# power_rev_1.net
KiCad netlist of a schematic drawn in EAGLE
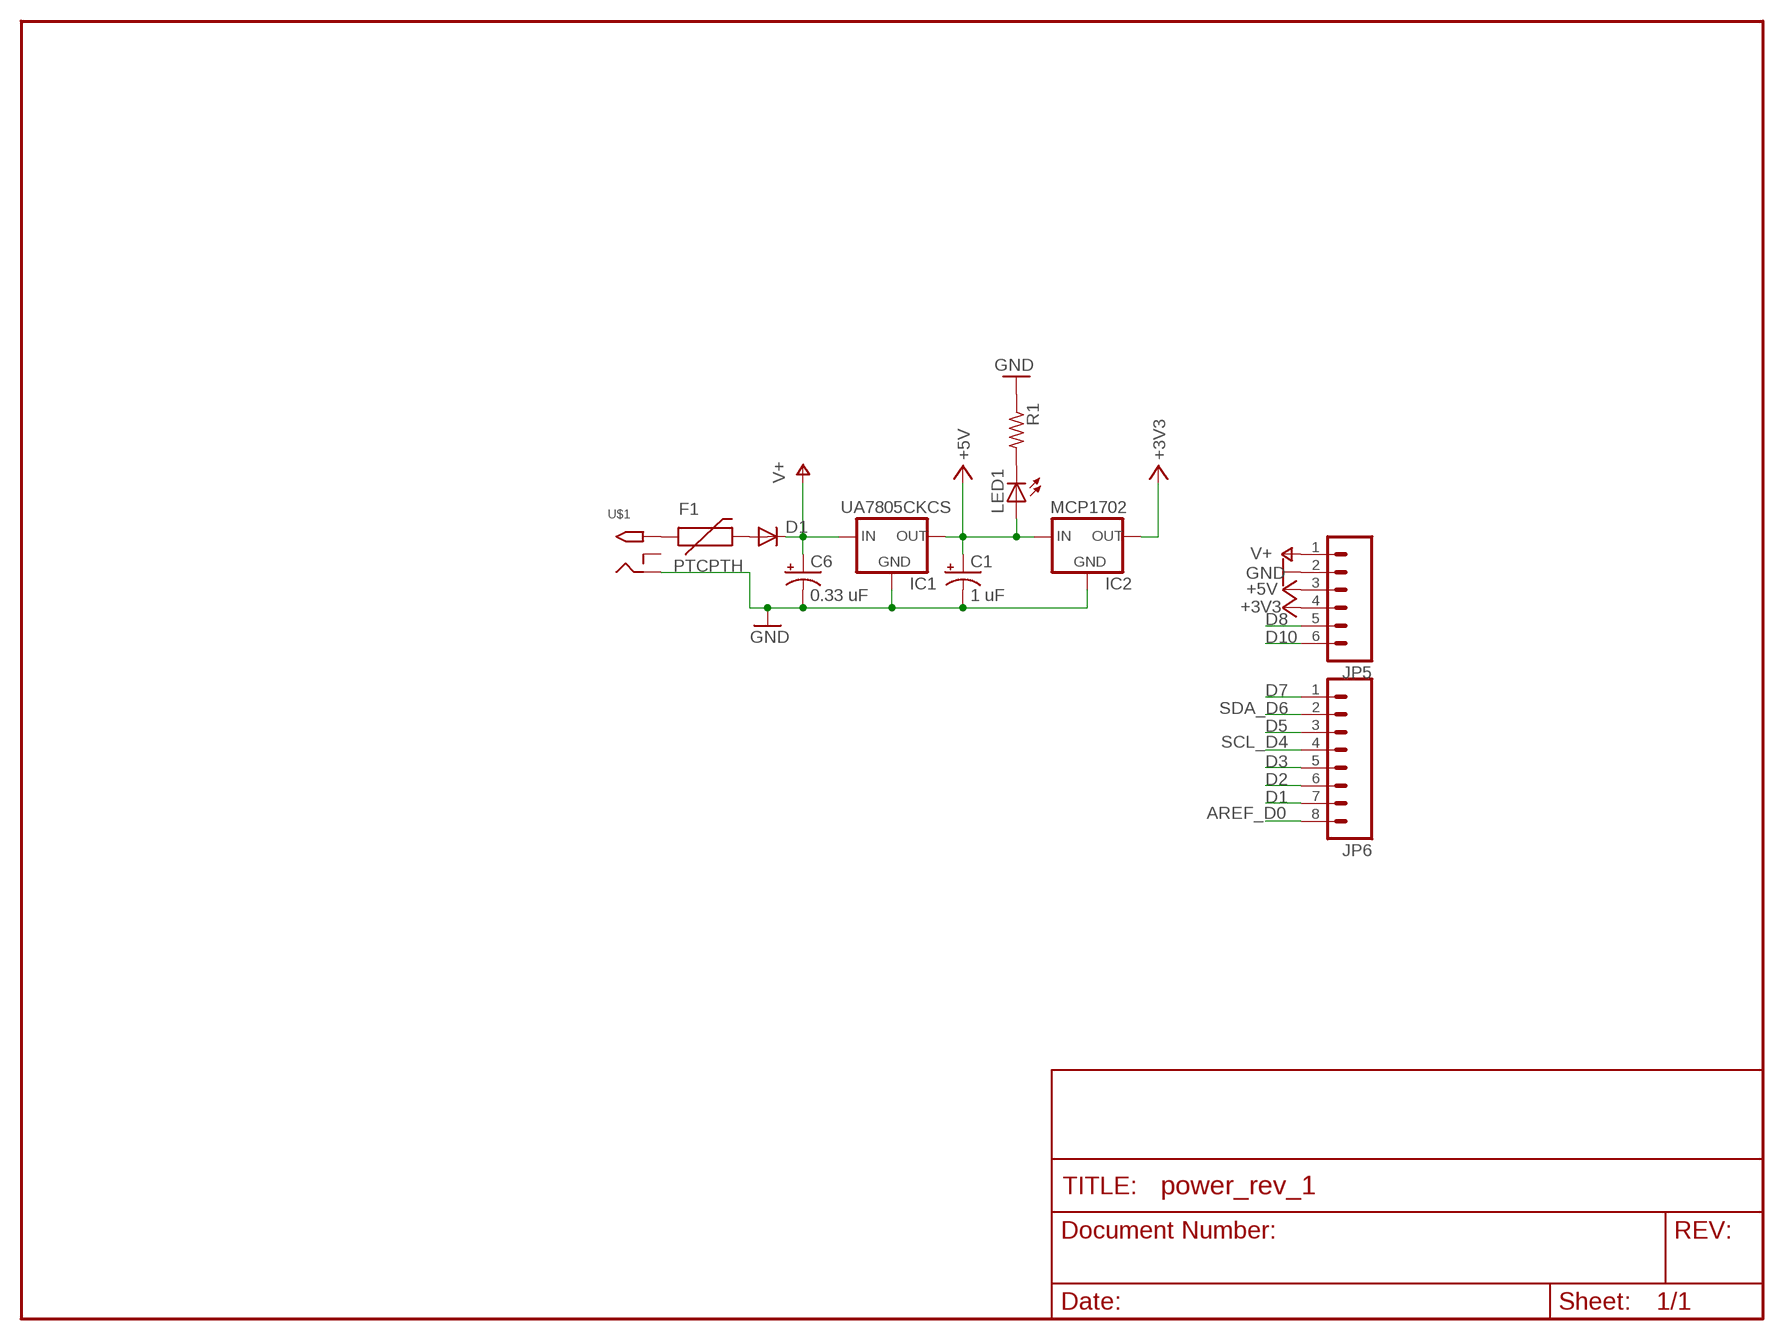
[diagram p0: schematic, sheet 1]

(export (version "E")
  (design (tool "Eeschema 10.0.6"))
  (components
    (comp (ref "C1")
      (value "1 uF")
      (footprint "eagle-import:CPOL-RADIAL-100UF-25V")
      (libsource (lib "eagle-import") (part "CAP_POLPTH1"))
    )
    (comp (ref "C6")
      (value "0.33 uF")
      (footprint "eagle-import:CPOL-RADIAL-100UF-25V")
      (libsource (lib "eagle-import") (part "CAP_POLPTH1"))
    )
    (comp (ref "D1")
      (value "DIODE1N4148")
      (footprint "eagle-import:DIODE-1N4148")
      (libsource (lib "eagle-import") (part "DIODE1N4148"))
    )
    (comp (ref "F1")
      (value "PTCPTH")
      (footprint "eagle-import:PTC")
      (libsource (lib "eagle-import") (part "PTCPTH"))
    )
    (comp (ref "IC1")
      (value "UA7805CKCS")
      (footprint "eagle-import:TO-220-ALT")
      (libsource (lib "eagle-import") (part "V_REG_78XX-TO-220"))
    )
    (comp (ref "IC2")
      (value "MCP1702")
      (footprint "eagle-import:TO92-INLINE")
      (libsource (lib "eagle-import") (part "MCP1700INLINE"))
    )
    (comp (ref "JP5")
      (value "M06SIP")
      (footprint "eagle-import:1X06")
      (libsource (lib "eagle-import") (part "M06SIP"))
    )
    (comp (ref "JP6")
      (value "M081X08")
      (footprint "eagle-import:1X08")
      (libsource (lib "eagle-import") (part "M081X08"))
    )
    (comp (ref "LED1")
      (value "LED3MM")
      (footprint "eagle-import:LED3MM")
      (libsource (lib "eagle-import") (part "LED3MM"))
    )
    (comp (ref "R1")
      (value "R-US_0204/2V")
      (footprint "eagle-import:0204V")
      (libsource (lib "eagle-import") (part "R-US_0204/2V"))
    )
    (comp (ref "U$1")
      (value "2.1MMJACKTHM")
      (footprint "eagle-import:PJ-102A")
      (libsource (lib "eagle-import") (part "2.1MMJACKTHM"))
    )
  )
  (nets
    (net (code "1") (name "+3V3") (class "Default")
      (node (ref "IC2") (pin "3") (pinfunction "OUT_3") (pintype "passive"))
      (node (ref "JP5") (pin "4") (pinfunction "4_4") (pintype "passive"))
    )
    (net (code "2") (name "+5V") (class "Default")
      (node (ref "C1") (pin "1") (pinfunction "+_1") (pintype "passive"))
      (node (ref "IC1") (pin "OUT") (pinfunction "OUT_OUT") (pintype "output"))
      (node (ref "IC2") (pin "2") (pinfunction "IN_2") (pintype "input"))
      (node (ref "JP5") (pin "3") (pinfunction "3_3") (pintype "passive"))
      (node (ref "LED1") (pin "A") (pinfunction "A_A") (pintype "passive"))
    )
    (net (code "3") (name "/AREF_D0") (class "Default")
      (node (ref "JP6") (pin "8") (pinfunction "8_8") (pintype "passive"))
    )
    (net (code "4") (name "/D1") (class "Default")
      (node (ref "JP6") (pin "7") (pinfunction "7_7") (pintype "passive"))
    )
    (net (code "5") (name "/D2") (class "Default")
      (node (ref "JP6") (pin "6") (pinfunction "6_6") (pintype "passive"))
    )
    (net (code "6") (name "/D3") (class "Default")
      (node (ref "JP6") (pin "5") (pinfunction "5_5") (pintype "passive"))
    )
    (net (code "7") (name "/D5") (class "Default")
      (node (ref "JP6") (pin "3") (pinfunction "3_3") (pintype "passive"))
    )
    (net (code "8") (name "/D7") (class "Default")
      (node (ref "JP6") (pin "1") (pinfunction "1_1") (pintype "passive"))
    )
    (net (code "9") (name "/D8") (class "Default")
      (node (ref "JP5") (pin "5") (pinfunction "5_5") (pintype "passive"))
    )
    (net (code "10") (name "/D10") (class "Default")
      (node (ref "JP5") (pin "6") (pinfunction "6_6") (pintype "passive"))
    )
    (net (code "11") (name "/SCL_D4") (class "Default")
      (node (ref "JP6") (pin "4") (pinfunction "4_4") (pintype "passive"))
    )
    (net (code "12") (name "/SDA_D6") (class "Default")
      (node (ref "JP6") (pin "2") (pinfunction "2_2") (pintype "passive"))
    )
    (net (code "13") (name "GND") (class "Default")
      (node (ref "C1") (pin "2") (pinfunction "-_2") (pintype "passive"))
      (node (ref "C6") (pin "2") (pinfunction "-_2") (pintype "passive"))
      (node (ref "IC1") (pin "GND") (pinfunction "GND_GND") (pintype "input"))
      (node (ref "IC2") (pin "1") (pinfunction "GND_1") (pintype "input"))
      (node (ref "JP5") (pin "2") (pinfunction "2_2") (pintype "passive"))
      (node (ref "R1") (pin "1") (pinfunction "1_1") (pintype "passive"))
      (node (ref "U$1") (pin "RING") (pinfunction "RING_RING") (pintype "bidirectional"))
    )
    (net (code "14") (name "Net-(F1-1)") (class "Default")
      (node (ref "F1") (pin "P$1") (pinfunction "1_P$1") (pintype "bidirectional"))
      (node (ref "U$1") (pin "TIP") (pinfunction "TIP_TIP") (pintype "bidirectional"))
    )
    (net (code "15") (name "Net-(F1-2)") (class "Default")
      (node (ref "D1") (pin "A") (pinfunction "A_A") (pintype "passive"))
      (node (ref "F1") (pin "P$2") (pinfunction "2_P$2") (pintype "bidirectional"))
    )
    (net (code "16") (name "Net-(LED1-C)") (class "Default")
      (node (ref "LED1") (pin "K") (pinfunction "C_K") (pintype "passive"))
      (node (ref "R1") (pin "2") (pinfunction "2_2") (pintype "passive"))
    )
    (net (code "17") (name "V+") (class "Default")
      (node (ref "C6") (pin "1") (pinfunction "+_1") (pintype "passive"))
      (node (ref "D1") (pin "C") (pinfunction "C_C") (pintype "passive"))
      (node (ref "IC1") (pin "IN") (pinfunction "IN_IN") (pintype "input"))
      (node (ref "JP5") (pin "1") (pinfunction "1_1") (pintype "passive"))
    )
    (net (code "18") (name "unconnected-(U$1-PadRING_SW)") (class "Default")
      (node (ref "U$1") (pin "RING_SW") (pinfunction "RING_SW_RING_SW") (pintype "bidirectional"))
    )
  )
)
